# S01-LAUNCHPAD.net
KiCad netlist of a schematic drawn in Altium Designer
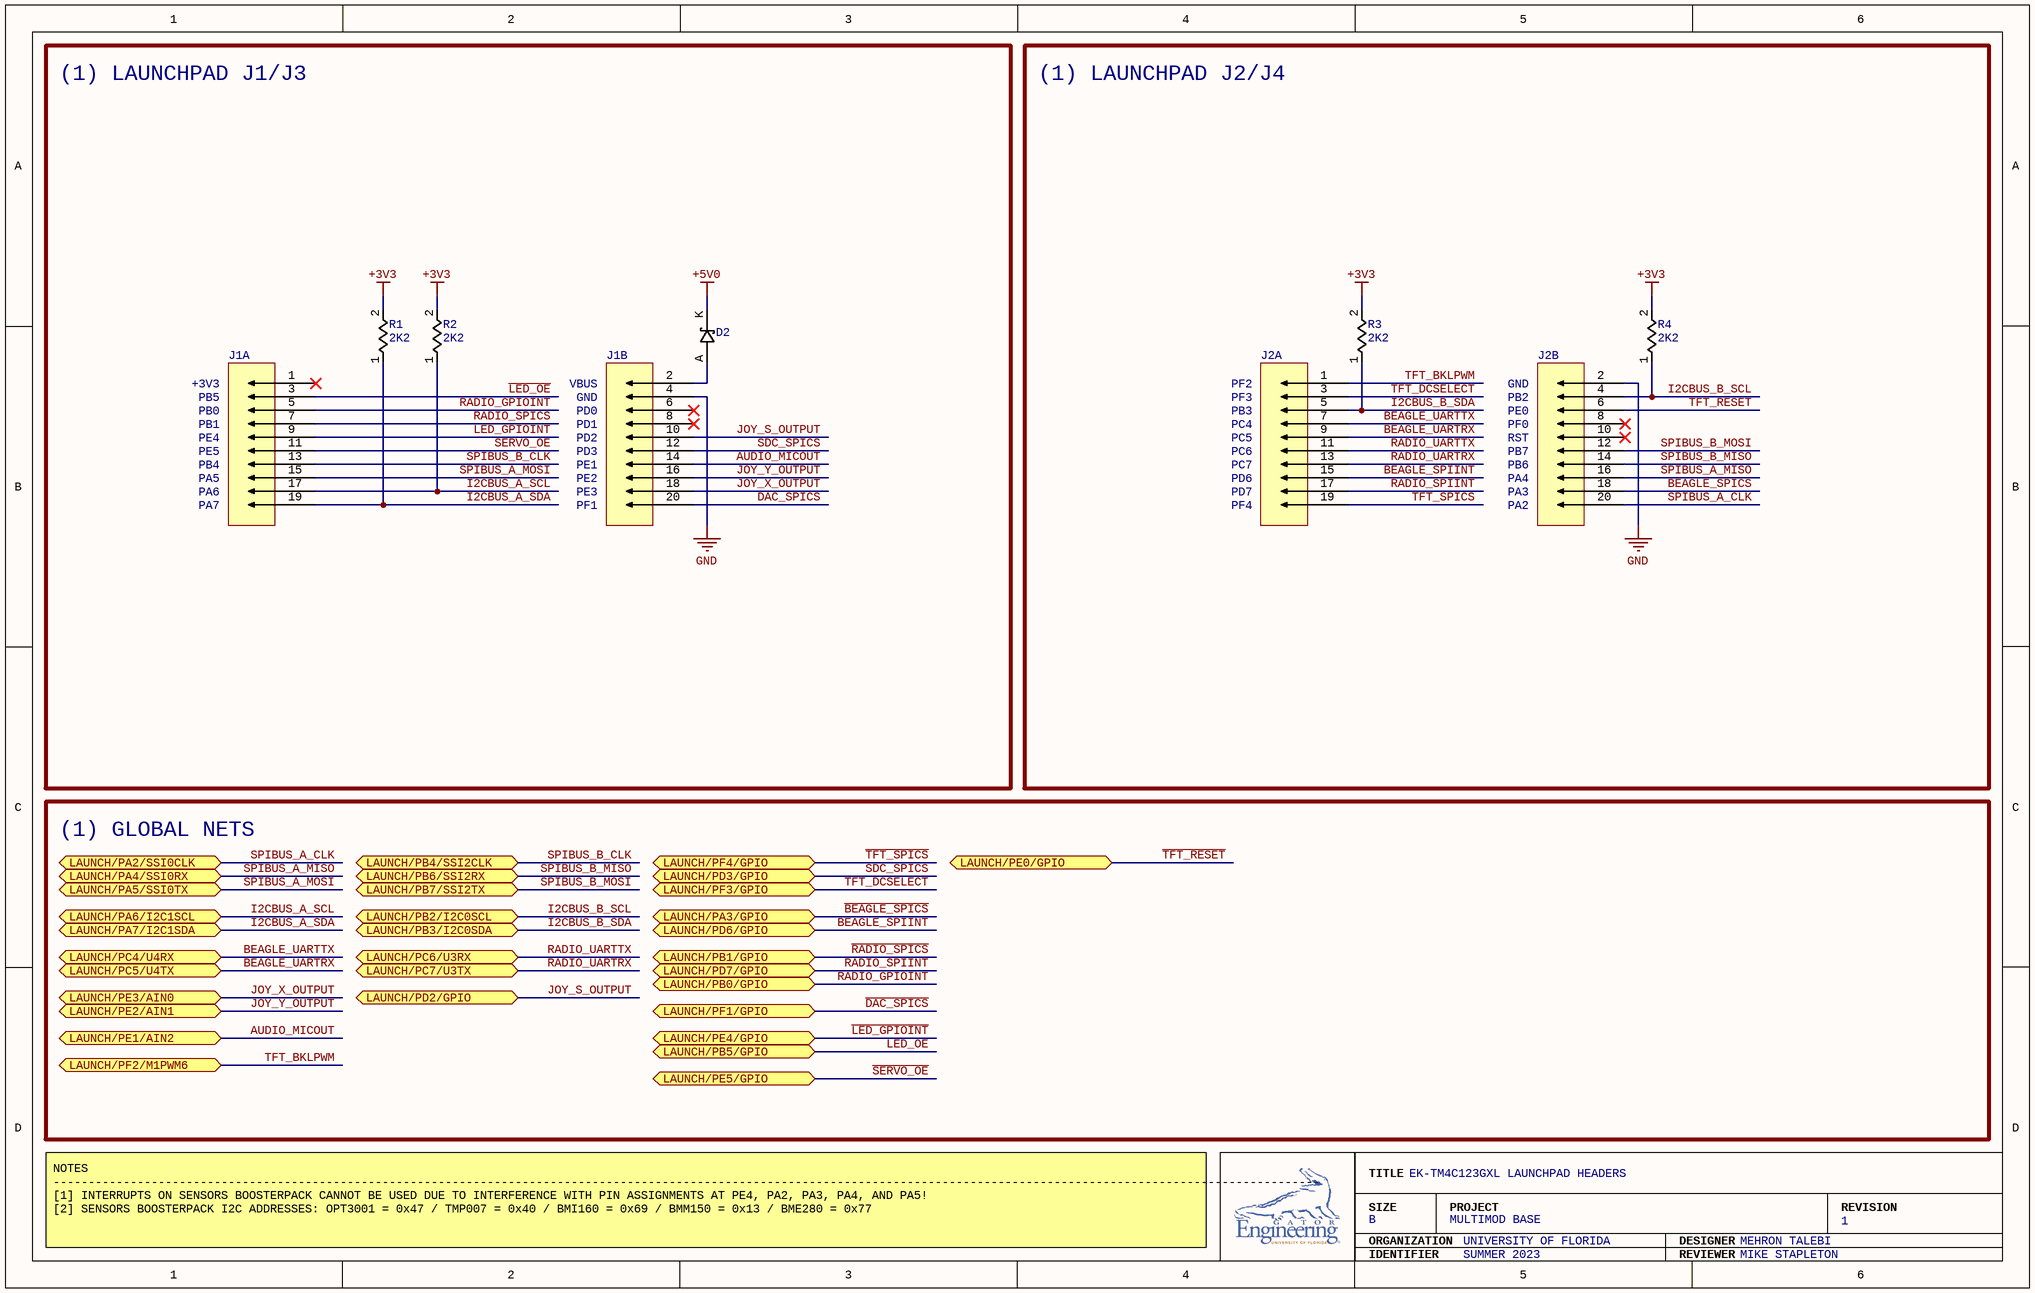
[diagram p0: S01-LAUNCHPAD.SchDoc]

(export (version "E")
  (design (tool "Eeschema 10.0.6"))
  (components
    (comp (ref "D2")
      (value "RBR5L30BDDTE25")
      (footprint "RBR5L30BDDTE25")
      (description "DIODE SCHOTTKY 30V 5A PMDS")
      (libsource (lib "Master") (part "RBR5L30BDDTE25"))
    )
    (comp (ref "J1")
      (value "95278-101-20LF")
      (footprint "95278-101-20LF")
      (description "CONN HEADER SMD 20POS 2.54MM")
      (libsource (lib "Master") (part "95278-101-20LF"))
    )
    (comp (ref "J2")
      (value "95278-101-20LF")
      (footprint "95278-101-20LF")
      (description "CONN HEADER SMD 20POS 2.54MM")
      (libsource (lib "Master") (part "95278-101-20LF"))
    )
    (comp (ref "R1")
      (value "2K2")
      (footprint "RC0805FR-072K2L")
      (description "RES 2.2K OHM 1% 1/8W 0805")
      (fields (field (name "TOLERANCE") "±1%"))
      (libsource (lib "Master") (part "RC0805FR-072K2L"))
    )
    (comp (ref "R2")
      (value "2K2")
      (footprint "RC0805FR-072K2L")
      (description "RES 2.2K OHM 1% 1/8W 0805")
      (fields (field (name "TOLERANCE") "±1%"))
      (libsource (lib "Master") (part "RC0805FR-072K2L"))
    )
    (comp (ref "R3")
      (value "2K2")
      (footprint "RC0805FR-072K2L")
      (description "RES 2.2K OHM 1% 1/8W 0805")
      (fields (field (name "TOLERANCE") "±1%"))
      (libsource (lib "Master") (part "RC0805FR-072K2L"))
    )
    (comp (ref "R4")
      (value "2K2")
      (footprint "RC0805FR-072K2L")
      (description "RES 2.2K OHM 1% 1/8W 0805")
      (fields (field (name "TOLERANCE") "±1%"))
      (libsource (lib "Master") (part "RC0805FR-072K2L"))
    )
  )
  (nets
    (net (code "1") (name "+3V3") (class "Default")
      (node (ref "R1") (pin "2") (pinfunction "2_2") (pintype "passive"))
      (node (ref "R2") (pin "2") (pinfunction "2_2") (pintype "passive"))
      (node (ref "R3") (pin "2") (pinfunction "2_2") (pintype "passive"))
      (node (ref "R4") (pin "2") (pinfunction "2_2") (pintype "passive"))
    )
    (net (code "2") (name "+5V0") (class "Default")
      (node (ref "D2") (pin "K") (pinfunction "+_K") (pintype "passive"))
    )
    (net (code "3") (name "/AUDIO_MICOUT") (class "Default")
      (node (ref "J1") (pin "14") (pinfunction "14_14") (pintype "passive"))
    )
    (net (code "4") (name "/BEAGLE_SPICS") (class "Default")
      (node (ref "J2") (pin "18") (pinfunction "18_18") (pintype "passive"))
    )
    (net (code "5") (name "/BEAGLE_SPIINT") (class "Default")
      (node (ref "J2") (pin "15") (pinfunction "15_15") (pintype "passive"))
    )
    (net (code "6") (name "/BEAGLE_UARTRX") (class "Default")
      (node (ref "J2") (pin "9") (pinfunction "9_9") (pintype "passive"))
    )
    (net (code "7") (name "/BEAGLE_UARTTX") (class "Default")
      (node (ref "J2") (pin "7") (pinfunction "7_7") (pintype "passive"))
    )
    (net (code "8") (name "/DAC_SPICS") (class "Default")
      (node (ref "J1") (pin "20") (pinfunction "20_20") (pintype "passive"))
    )
    (net (code "9") (name "/I2CBUS_A_SCL") (class "Default")
      (node (ref "J1") (pin "17") (pinfunction "17_17") (pintype "passive"))
      (node (ref "R2") (pin "1") (pinfunction "1_1") (pintype "passive"))
    )
    (net (code "10") (name "/I2CBUS_A_SDA") (class "Default")
      (node (ref "J1") (pin "19") (pinfunction "19_19") (pintype "passive"))
      (node (ref "R1") (pin "1") (pinfunction "1_1") (pintype "passive"))
    )
    (net (code "11") (name "/I2CBUS_B_SCL") (class "Default")
      (node (ref "J2") (pin "4") (pinfunction "4_4") (pintype "passive"))
      (node (ref "R4") (pin "1") (pinfunction "1_1") (pintype "passive"))
    )
    (net (code "12") (name "/I2CBUS_B_SDA") (class "Default")
      (node (ref "J2") (pin "5") (pinfunction "5_5") (pintype "passive"))
      (node (ref "R3") (pin "1") (pinfunction "1_1") (pintype "passive"))
    )
    (net (code "13") (name "/JOY_S_OUTPUT") (class "Default")
      (node (ref "J1") (pin "10") (pinfunction "10_10") (pintype "passive"))
    )
    (net (code "14") (name "/JOY_X_OUTPUT") (class "Default")
      (node (ref "J1") (pin "18") (pinfunction "18_18") (pintype "passive"))
    )
    (net (code "15") (name "/JOY_Y_OUTPUT") (class "Default")
      (node (ref "J1") (pin "16") (pinfunction "16_16") (pintype "passive"))
    )
    (net (code "16") (name "/LED_GPIOINT") (class "Default")
      (node (ref "J1") (pin "9") (pinfunction "9_9") (pintype "passive"))
    )
    (net (code "17") (name "/LED_OE") (class "Default")
      (node (ref "J1") (pin "3") (pinfunction "3_3") (pintype "passive"))
    )
    (net (code "18") (name "/RADIO_GPIOINT") (class "Default")
      (node (ref "J1") (pin "5") (pinfunction "5_5") (pintype "passive"))
    )
    (net (code "19") (name "/RADIO_SPICS") (class "Default")
      (node (ref "J1") (pin "7") (pinfunction "7_7") (pintype "passive"))
    )
    (net (code "20") (name "/RADIO_SPIINT") (class "Default")
      (node (ref "J2") (pin "17") (pinfunction "17_17") (pintype "passive"))
    )
    (net (code "21") (name "/RADIO_UARTRX") (class "Default")
      (node (ref "J2") (pin "13") (pinfunction "13_13") (pintype "passive"))
    )
    (net (code "22") (name "/RADIO_UARTTX") (class "Default")
      (node (ref "J2") (pin "11") (pinfunction "11_11") (pintype "passive"))
    )
    (net (code "23") (name "/SDC_SPICS") (class "Default")
      (node (ref "J1") (pin "12") (pinfunction "12_12") (pintype "passive"))
    )
    (net (code "24") (name "/SERVO_OE") (class "Default")
      (node (ref "J1") (pin "11") (pinfunction "11_11") (pintype "passive"))
    )
    (net (code "25") (name "/SPIBUS_A_CLK") (class "Default")
      (node (ref "J2") (pin "20") (pinfunction "20_20") (pintype "passive"))
    )
    (net (code "26") (name "/SPIBUS_A_MISO") (class "Default")
      (node (ref "J2") (pin "16") (pinfunction "16_16") (pintype "passive"))
    )
    (net (code "27") (name "/SPIBUS_A_MOSI") (class "Default")
      (node (ref "J1") (pin "15") (pinfunction "15_15") (pintype "passive"))
    )
    (net (code "28") (name "/SPIBUS_B_CLK") (class "Default")
      (node (ref "J1") (pin "13") (pinfunction "13_13") (pintype "passive"))
    )
    (net (code "29") (name "/SPIBUS_B_MISO") (class "Default")
      (node (ref "J2") (pin "14") (pinfunction "14_14") (pintype "passive"))
    )
    (net (code "30") (name "/SPIBUS_B_MOSI") (class "Default")
      (node (ref "J2") (pin "12") (pinfunction "12_12") (pintype "passive"))
    )
    (net (code "31") (name "/TFT_BKLPWM") (class "Default")
      (node (ref "J2") (pin "1") (pinfunction "1_1") (pintype "passive"))
    )
    (net (code "32") (name "/TFT_DCSELECT") (class "Default")
      (node (ref "J2") (pin "3") (pinfunction "3_3") (pintype "passive"))
    )
    (net (code "33") (name "/TFT_RESET") (class "Default")
      (node (ref "J2") (pin "6") (pinfunction "6_6") (pintype "passive"))
    )
    (net (code "34") (name "/TFT_SPICS") (class "Default")
      (node (ref "J2") (pin "19") (pinfunction "19_19") (pintype "passive"))
    )
    (net (code "35") (name "GND") (class "Default")
      (node (ref "J1") (pin "4") (pinfunction "4_4") (pintype "passive"))
      (node (ref "J2") (pin "2") (pinfunction "2_2") (pintype "passive"))
    )
    (net (code "36") (name "Net-(D2--)") (class "Default")
      (node (ref "D2") (pin "A") (pinfunction "-_A") (pintype "passive"))
      (node (ref "J1") (pin "2") (pinfunction "2_2") (pintype "passive"))
    )
    (net (code "37") (name "unconnected-(J1-Pad1)") (class "Default")
      (node (ref "J1") (pin "1") (pinfunction "1_1") (pintype "passive+no_connect"))
    )
    (net (code "38") (name "unconnected-(J1-Pad6)") (class "Default")
      (node (ref "J1") (pin "6") (pinfunction "6_6") (pintype "passive+no_connect"))
    )
    (net (code "39") (name "unconnected-(J1-Pad8)") (class "Default")
      (node (ref "J1") (pin "8") (pinfunction "8_8") (pintype "passive+no_connect"))
    )
    (net (code "40") (name "unconnected-(J2-Pad8)") (class "Default")
      (node (ref "J2") (pin "8") (pinfunction "8_8") (pintype "passive+no_connect"))
    )
    (net (code "41") (name "unconnected-(J2-Pad10)") (class "Default")
      (node (ref "J2") (pin "10") (pinfunction "10_10") (pintype "passive+no_connect"))
    )
  )
)
